# Drivers.net
KiCad netlist of a schematic drawn in Altium Designer
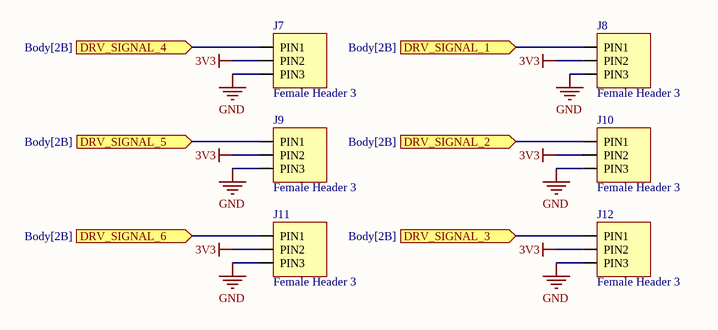
[diagram p0: Drivers.SchDoc]

(export (version "E")
  (design (tool "Eeschema 10.0.6"))
  (components
    (comp (ref "J7")
      (value "Female Header 3")
      (footprint "FEMALE HEADER 3")
      (libsource (lib "StandartComponents") (part "Female Header 3"))
    )
    (comp (ref "J8")
      (value "Female Header 3")
      (footprint "FEMALE HEADER 3")
      (libsource (lib "StandartComponents") (part "Female Header 3"))
    )
    (comp (ref "J9")
      (value "Female Header 3")
      (footprint "FEMALE HEADER 3")
      (libsource (lib "StandartComponents") (part "Female Header 3"))
    )
    (comp (ref "J10")
      (value "Female Header 3")
      (footprint "FEMALE HEADER 3")
      (libsource (lib "StandartComponents") (part "Female Header 3"))
    )
    (comp (ref "J11")
      (value "Female Header 3")
      (footprint "FEMALE HEADER 3")
      (libsource (lib "StandartComponents") (part "Female Header 3"))
    )
    (comp (ref "J12")
      (value "Female Header 3")
      (footprint "FEMALE HEADER 3")
      (libsource (lib "StandartComponents") (part "Female Header 3"))
    )
  )
  (nets
    (net (code "1") (name "/DRV_SIGNAL_1") (class "Default")
      (node (ref "J8") (pin "PIN1") (pinfunction "PIN1_PIN1") (pintype "passive"))
    )
    (net (code "2") (name "/DRV_SIGNAL_2") (class "Default")
      (node (ref "J10") (pin "PIN1") (pinfunction "PIN1_PIN1") (pintype "passive"))
    )
    (net (code "3") (name "/DRV_SIGNAL_3") (class "Default")
      (node (ref "J12") (pin "PIN1") (pinfunction "PIN1_PIN1") (pintype "passive"))
    )
    (net (code "4") (name "/DRV_SIGNAL_4") (class "Default")
      (node (ref "J7") (pin "PIN1") (pinfunction "PIN1_PIN1") (pintype "passive"))
    )
    (net (code "5") (name "/DRV_SIGNAL_5") (class "Default")
      (node (ref "J9") (pin "PIN1") (pinfunction "PIN1_PIN1") (pintype "passive"))
    )
    (net (code "6") (name "/DRV_SIGNAL_6") (class "Default")
      (node (ref "J11") (pin "PIN1") (pinfunction "PIN1_PIN1") (pintype "passive"))
    )
    (net (code "7") (name "3V3") (class "Default")
      (node (ref "J10") (pin "PIN2") (pinfunction "PIN2_PIN2") (pintype "passive"))
      (node (ref "J11") (pin "PIN2") (pinfunction "PIN2_PIN2") (pintype "passive"))
      (node (ref "J12") (pin "PIN2") (pinfunction "PIN2_PIN2") (pintype "passive"))
      (node (ref "J7") (pin "PIN2") (pinfunction "PIN2_PIN2") (pintype "passive"))
      (node (ref "J8") (pin "PIN2") (pinfunction "PIN2_PIN2") (pintype "passive"))
      (node (ref "J9") (pin "PIN2") (pinfunction "PIN2_PIN2") (pintype "passive"))
    )
    (net (code "8") (name "GND") (class "Default")
      (node (ref "J10") (pin "PIN3") (pinfunction "PIN3_PIN3") (pintype "passive"))
      (node (ref "J11") (pin "PIN3") (pinfunction "PIN3_PIN3") (pintype "passive"))
      (node (ref "J12") (pin "PIN3") (pinfunction "PIN3_PIN3") (pintype "passive"))
      (node (ref "J7") (pin "PIN3") (pinfunction "PIN3_PIN3") (pintype "passive"))
      (node (ref "J8") (pin "PIN3") (pinfunction "PIN3_PIN3") (pintype "passive"))
      (node (ref "J9") (pin "PIN3") (pinfunction "PIN3_PIN3") (pintype "passive"))
    )
  )
)
